# lab_8.net
KiCad netlist of a schematic drawn in EAGLE
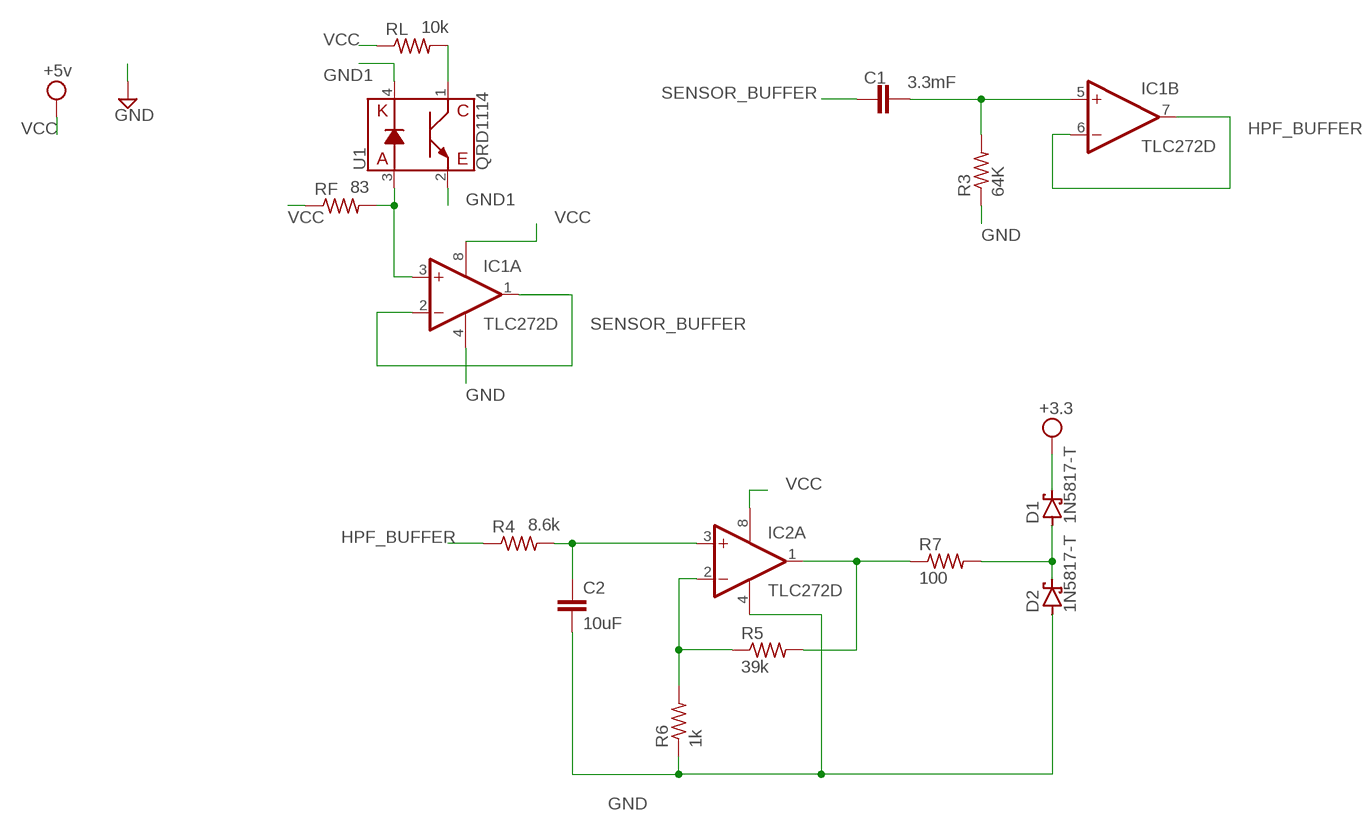
[diagram p0: schematic, sheet 1]

(export (version "E")
  (design (tool "Eeschema 10.0.6"))
  (components
    (comp (ref "C1")
      (value "3.3mF")
      (footprint "eagle-import:C025-025X050")
      (libsource (lib "eagle-import") (part "C-EU025-025X050"))
    )
    (comp (ref "C2")
      (value "10uF")
      (footprint "eagle-import:C025-025X050")
      (libsource (lib "eagle-import") (part "C-EU025-025X050"))
    )
    (comp (ref "D1")
      (value "1N5817-T")
      (footprint "eagle-import:DO41-7.6")
      (libsource (lib "eagle-import") (part "1N5817-T"))
    )
    (comp (ref "D2")
      (value "1N5817-T")
      (footprint "eagle-import:DO41-7.6")
      (libsource (lib "eagle-import") (part "1N5817-T"))
    )
    (comp (ref "IC1")
      (value "TLC272D")
      (footprint "eagle-import:SO08")
      (libsource (lib "eagle-import") (part "TLC272D"))
    )
    (comp (ref "IC2")
      (value "TLC272D")
      (footprint "eagle-import:SO08")
      (libsource (lib "eagle-import") (part "TLC272D"))
    )
    (comp (ref "R3")
      (value "64K")
      (footprint "eagle-import:R0805")
      (libsource (lib "eagle-import") (part "R-US_R0805"))
    )
    (comp (ref "R4")
      (value "8.6k")
      (footprint "eagle-import:R0805")
      (libsource (lib "eagle-import") (part "R-US_R0805"))
    )
    (comp (ref "R5")
      (value "39k")
      (footprint "eagle-import:R0805")
      (libsource (lib "eagle-import") (part "R-US_R0805"))
    )
    (comp (ref "R6")
      (value "1k")
      (footprint "eagle-import:R0805")
      (libsource (lib "eagle-import") (part "R-US_R0805"))
    )
    (comp (ref "R7")
      (value "100")
      (footprint "eagle-import:R0805")
      (libsource (lib "eagle-import") (part "R-US_R0805"))
    )
    (comp (ref "RF")
      (value "83")
      (footprint "eagle-import:R0805")
      (libsource (lib "eagle-import") (part "R-US_R0805"))
    )
    (comp (ref "RL")
      (value "10k")
      (footprint "eagle-import:R0805")
      (libsource (lib "eagle-import") (part "R-US_R0805"))
    )
    (comp (ref "U1")
      (value "QRD1114")
      (footprint "eagle-import:QRD1114")
      (libsource (lib "eagle-import") (part "QRD1114"))
    )
  )
  (nets
    (net (code "1") (name "+3.3") (class "Default")
      (node (ref "D1") (pin "C") (pinfunction "C_C") (pintype "passive"))
      (node (ref "IC1") (pin "8") (pinfunction "V+_8") (pintype "power_in"))
      (node (ref "IC2") (pin "8") (pinfunction "V+_8") (pintype "power_in"))
      (node (ref "RF") (pin "1") (pinfunction "1_1") (pintype "passive"))
      (node (ref "RL") (pin "1") (pinfunction "1_1") (pintype "passive"))
      (node (ref "RL") (pin "2") (pinfunction "2_2") (pintype "passive"))
      (node (ref "U1") (pin "1") (pinfunction "C_1") (pintype "bidirectional"))
    )
    (net (code "2") (name "/GND1") (class "Default")
      (node (ref "U1") (pin "2") (pinfunction "E_2") (pintype "bidirectional"))
      (node (ref "U1") (pin "4") (pinfunction "K_4") (pintype "bidirectional"))
    )
    (net (code "3") (name "/HPF_BUFFER") (class "Default")
      (node (ref "IC1") (pin "6") (pinfunction "-IN_6") (pintype "input"))
      (node (ref "IC1") (pin "7") (pinfunction "OUT_7") (pintype "output"))
      (node (ref "R4") (pin "1") (pinfunction "1_1") (pintype "passive"))
    )
    (net (code "4") (name "/SENSOR_BUFFER") (class "Default")
      (node (ref "C1") (pin "1") (pinfunction "1_1") (pintype "passive"))
      (node (ref "IC1") (pin "1") (pinfunction "OUT_1") (pintype "output"))
      (node (ref "IC1") (pin "2") (pinfunction "-IN_2") (pintype "input"))
    )
    (net (code "5") (name "GND") (class "Default")
      (node (ref "C2") (pin "2") (pinfunction "2_2") (pintype "passive"))
      (node (ref "D2") (pin "A") (pinfunction "A_A") (pintype "passive"))
      (node (ref "IC1") (pin "4") (pinfunction "V-_4") (pintype "power_in"))
      (node (ref "IC2") (pin "4") (pinfunction "V-_4") (pintype "power_in"))
      (node (ref "R3") (pin "1") (pinfunction "1_1") (pintype "passive"))
      (node (ref "R6") (pin "1") (pinfunction "1_1") (pintype "passive"))
    )
    (net (code "6") (name "Net-(D1-PadA)") (class "Default")
      (node (ref "D1") (pin "A") (pinfunction "A_A") (pintype "passive"))
      (node (ref "D2") (pin "C") (pinfunction "C_C") (pintype "passive"))
      (node (ref "R7") (pin "2") (pinfunction "2_2") (pintype "passive"))
    )
    (net (code "7") (name "Net-(IC1A-+IN)") (class "Default")
      (node (ref "IC1") (pin "3") (pinfunction "+IN_3") (pintype "input"))
      (node (ref "RF") (pin "2") (pinfunction "2_2") (pintype "passive"))
      (node (ref "U1") (pin "3") (pinfunction "A_3") (pintype "bidirectional"))
    )
    (net (code "8") (name "Net-(IC1B-+IN)") (class "Default")
      (node (ref "C1") (pin "2") (pinfunction "2_2") (pintype "passive"))
      (node (ref "IC1") (pin "5") (pinfunction "+IN_5") (pintype "input"))
      (node (ref "R3") (pin "2") (pinfunction "2_2") (pintype "passive"))
    )
    (net (code "9") (name "Net-(IC2A-+IN)") (class "Default")
      (node (ref "C2") (pin "1") (pinfunction "1_1") (pintype "passive"))
      (node (ref "IC2") (pin "3") (pinfunction "+IN_3") (pintype "input"))
      (node (ref "R4") (pin "2") (pinfunction "2_2") (pintype "passive"))
    )
    (net (code "10") (name "Net-(IC2A--IN)") (class "Default")
      (node (ref "IC2") (pin "2") (pinfunction "-IN_2") (pintype "input"))
      (node (ref "R5") (pin "1") (pinfunction "1_1") (pintype "passive"))
      (node (ref "R6") (pin "2") (pinfunction "2_2") (pintype "passive"))
    )
    (net (code "11") (name "Net-(IC2A-OUT)") (class "Default")
      (node (ref "IC2") (pin "1") (pinfunction "OUT_1") (pintype "output"))
      (node (ref "R5") (pin "2") (pinfunction "2_2") (pintype "passive"))
      (node (ref "R7") (pin "1") (pinfunction "1_1") (pintype "passive"))
    )
  )
)
